# Buck.net
KiCad netlist of a schematic drawn in Altium Designer
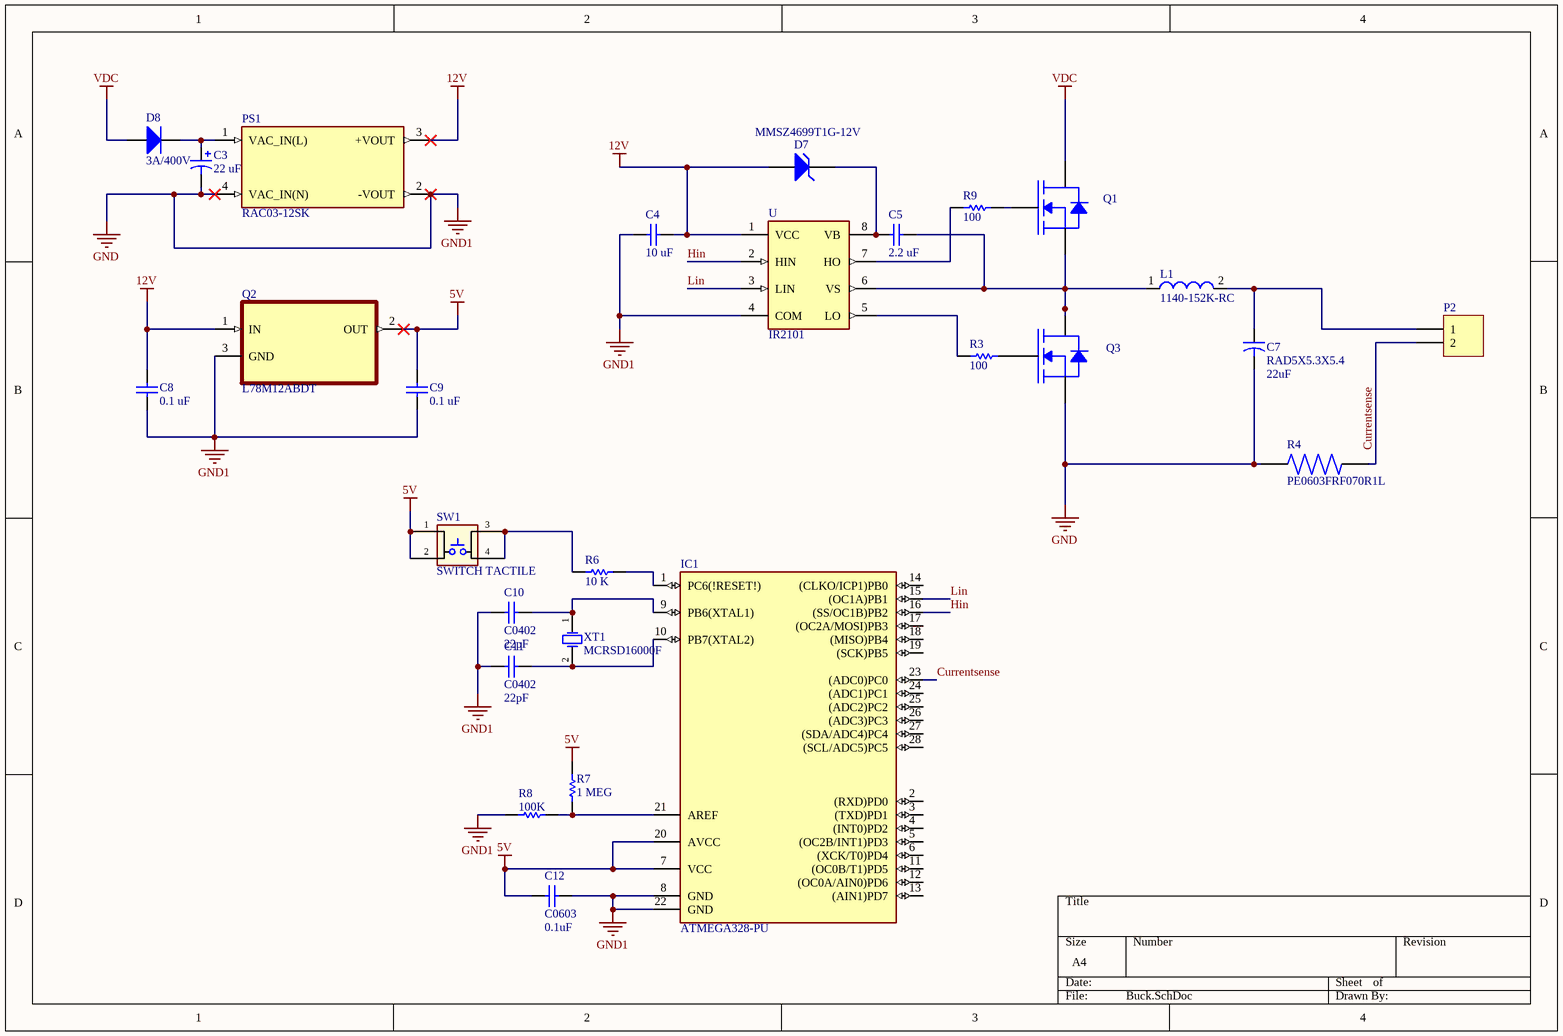
[diagram p0: Buck.SchDoc]

(export (version "E")
  (design (tool "Eeschema 10.0.6"))
  (components
    (comp (ref "C3")
      (value "22 uF")
      (footprint "CAP-12.25X25")
      (description "22 uF Electrlytic capacitor")
      (fields (field (name "Comment") "EEUED2G220") (field (name "PUBLISHER") "Altium Limited"))
      (libsource (lib "Viva") (part "EEUED2G220"))
    )
    (comp (ref "C4")
      (value "10 uF")
      (footprint "1206")
      (description "10 uF X7R Ceremic Capacitor")
      (fields (field (name "Comment") "MC1206B106K160CT") (field (name "PUBLISHER") "Sinan"))
      (libsource (lib "Viva") (part "MC1206B106K160CT"))
    )
    (comp (ref "C5")
      (value "2.2 uF")
      (footprint "0805")
      (description "2.2 uF X7R Ceremic Capacitor")
      (fields
        (field (name "TOLERANCE") "%10")
        (field (name "Comment") "C2012X7R1C225K")
        (field (name "PUBLISHER") "Sinan")
      )
      (libsource (lib "Viva") (part "C2012X7R1C225K"))
    )
    (comp (ref "C7")
      (value "22uF")
      (footprint "RAD5.3X5.3X5.0")
      (description "CAP ALUM 22UF 20% 35V SMD 5X5.3X5.4")
      (fields (field (name "MANUFACTURER") "PANASONIC") (field (name "PACKAGE REFERENCE") "RAD5X5.3X5.4"))
      (libsource (lib "CAPACITOR_LIB") (part "CAP ALUM 22UF 20% 35V SMD 5X5.3X5.4"))
    )
    (comp (ref "C8")
      (value "0.1 uF")
      (footprint "0603")
      (description "0.1uF X7R Ceramic Capacitor")
      (fields
        (field (name "TOLERANCE") "%5")
        (field (name "Comment") "*Value")
        (field (name "PUBLISHER") "Baris")
      )
      (libsource (lib "Viva") (part "C0603C104K3RACTU"))
    )
    (comp (ref "C9")
      (value "0.1 uF")
      (footprint "0603")
      (description "0.1uF X7R Ceramic Capacitor")
      (fields
        (field (name "TOLERANCE") "%5")
        (field (name "Comment") "*Value")
        (field (name "PUBLISHER") "Baris")
      )
      (libsource (lib "Viva") (part "C0603C104K3RACTU"))
    )
    (comp (ref "C10")
      (value "22pF")
      (footprint "C0402N")
      (description "CAP CER 22PF 5% 50V NP0 SMD 0402")
      (fields (field (name "MANUFACTURER") "SAMSUNG ELECTRO") (field (name "PACKAGE REFERENCE") "C0402"))
      (libsource (lib "CAPACITOR_LIB") (part "CAP CER 22PF 5% 50V NP0 SMD 0402"))
    )
    (comp (ref "C11")
      (value "22pF")
      (footprint "C0402N")
      (description "CAP CER 22PF 5% 50V NP0 SMD 0402")
      (fields (field (name "MANUFACTURER") "SAMSUNG ELECTRO") (field (name "PACKAGE REFERENCE") "C0402"))
      (libsource (lib "CAPACITOR_LIB") (part "CAP CER 22PF 5% 50V NP0 SMD 0402"))
    )
    (comp (ref "C12")
      (value "0.1uF")
      (footprint "C0603N")
      (description "CAP CER 0.1UF 10% 16V X7R SMD 0603")
      (fields (field (name "MANUFACTURER") "MURATA") (field (name "PACKAGE REFERENCE") "C0603"))
      (libsource (lib "CAPACITOR_LIB") (part "CAP CER 0.1UF 10% 16V X7R SMD 0603"))
    )
    (comp (ref "D7")
      (value "MMSZ4699T1G-12V")
      (footprint "SOD123")
      (description "DIODE ZENER 12V 500MW SOD123")
      (fields (field (name "PUBLISHER") "Baris"))
      (libsource (lib "Viva") (part "MMSZ4699T1G"))
    )
    (comp (ref "D8")
      (value "3A/400V")
      (footprint "DO201AD")
      (description "DIODE GEN PURP 400V 3A DO201AD")
      (fields
        (field (name "MANUFACTURER") "DIODES INC.")
        (field (name "Comment") "DIODE GEN PURP 400V 3A DO201AD - 1N5404")
      )
      (libsource (lib "DISCRETE_LIB") (part "DIODE GEN PURP 400V 3A DO201AD - 1N5404"))
    )
    (comp (ref "IC1")
      (value "ATMEGA328-PU")
      (footprint "DIL28")
      (description "AVR AVRÂ® ATmega Microcontroller IC 8-Bit 20MHz 32KB _16K x 16_ FLASH 28-PDIP")
      (fields (field (name "MF") "Microchip Technology"))
      (libsource (lib "ATMEGA328-PU") (part "ATMEGA328-PU"))
    )
    (comp (ref "L1")
      (value "1140-152K-RC")
      (footprint "INDRD2921W163D3810H2616P")
      (description "1.5mH Unshielded Wirewound Inductor 2.9A 324mOhm Max Radial")
      (fields (field (name "MF") "Bourns"))
      (libsource (lib "1140-152K-RC") (part "1140-152K-RC"))
    )
    (comp (ref "P2")
      (value "Konnektör")
      (footprint "250-202")
      (description "2 pos power connector")
      (fields (field (name "PUBLISHER") "Sinan"))
      (libsource (lib "Viva") (part "250-202"))
    )
    (comp (ref "PS1")
      (value "RAC03-12SK")
      (footprint "CONV_RAC03-12SK")
      (description "Enclosed AC DC Converters 1 Uitgang 12V 250mA 85 ~ 264 VAC, 120 ~ 370 VDC Input")
      (fields (field (name "MF") "Recom Power"))
      (libsource (lib "RAC03-12SK") (part "RAC03-12SK"))
    )
    (comp (ref "Q1")
      (value "LSIC1MO120E0080")
      (footprint "TO-247-3L")
      (description "LittleFuse SIC mosfet")
      (fields (field (name "PUBLISHER") "Baris"))
      (libsource (lib "Viva") (part "LSIC1MO120E0080"))
    )
    (comp (ref "Q2")
      (value "L78M12ABDT")
      (footprint "TO225P972X240-3N")
      (description "Linear Voltage Regulator IC 1 Output 500mA DPAK")
      (fields (field (name "MF") "STMicroelectronics"))
      (libsource (lib "L78M12ABDT") (part "L78M12ABDT"))
    )
    (comp (ref "Q3")
      (value "LSIC1MO120E0080")
      (footprint "TO-247-3L")
      (description "LittleFuse SIC mosfet")
      (fields (field (name "PUBLISHER") "Baris"))
      (libsource (lib "Viva") (part "LSIC1MO120E0080"))
    )
    (comp (ref "R3")
      (value "100")
      (footprint "1206")
      (description "100 ohm 1206 package resistor")
      (fields (field (name "Comment") "*Value") (field (name "PUBLISHER") "Baris"))
      (libsource (lib "Viva") (part "MC0125W12061100R"))
    )
    (comp (ref "R4")
      (value "PE0603FRF070R1L")
      (footprint "RESC1507X55N")
      (libsource (lib "PE0603FRF070R1L") (part "PE0603FRF070R1L"))
    )
    (comp (ref "R6")
      (value "10 K")
      (footprint "0603")
      (description "10k ohm 0603 package resistor")
      (fields
        (field (name "TOLERANCE") "5%")
        (field (name "Comment") "ERJ3GEYJ103V")
        (field (name "PUBLISHER") "Sinan")
      )
      (libsource (lib "Viva") (part "ERJ3GEYJ103V"))
    )
    (comp (ref "R7")
      (value "1 MEG")
      (footprint "0603")
      (description "1 MEG ohm 0603 package resistor")
      (fields (field (name "Comment") "Resistor") (field (name "PUBLISHER") "Sinan"))
      (libsource (lib "Viva") (part "MC0063W060311M"))
    )
    (comp (ref "R8")
      (value "100K")
      (footprint "0603")
      (description "100Kohm 0603package resistor")
      (fields (field (name "Comment") "MC0063W06031100K") (field (name "PUBLISHER") "Baris"))
      (libsource (lib "Viva") (part "MC0063W06031100K"))
    )
    (comp (ref "R9")
      (value "100")
      (footprint "1206")
      (description "100 ohm 1206 package resistor")
      (fields (field (name "Comment") "*Value") (field (name "PUBLISHER") "Baris"))
      (libsource (lib "Viva") (part "MC0125W12061100R"))
    )
    (comp (ref "SW1")
      (value "SWITCH TACTILE")
      (footprint "SWITCH_TACHTILE_SMD")
      (description "SWITCH TACTILE (SPST NO) TOP ACTUATED SURFACE MOUNT")
      (fields (field (name "MANUFACTURER") "C&K Components"))
      (libsource (lib "CONNECTOR_LIB") (part "SWITCH TACTILE"))
    )
    (comp (ref "U")
      (value "IR2101")
      (footprint "DIL08")
      (description "Half-Bridge Gate Driver IC Non-Inverting 8-PDIP")
      (fields (field (name "MF") "Infineon"))
      (libsource (lib "IR2101 (1)") (part "IR2101"))
    )
    (comp (ref "XT1")
      (value "MCRSD16000F")
      (footprint "XTAL_11.4MMX 4.7MM")
      (description "CRYSTAL 16MHZ 18PF")
      (fields (field (name "MANUFACTURER") "MULTICOMP"))
      (libsource (lib "DISCRETE_LIB") (part "CRYSTAL 16MHZ 18PF"))
    )
  )
  (nets
    (net (code "1") (name "/Currentsense") (class "Default")
      (node (ref "IC1") (pin "23") (pinfunction "(ADC0)PC0_23") (pintype "bidirectional"))
      (node (ref "P2") (pin "2") (pinfunction "2_2") (pintype "passive"))
      (node (ref "R4") (pin "1") (pinfunction "1_1") (pintype "passive"))
    )
    (net (code "2") (name "/Hin") (class "Default")
      (node (ref "IC1") (pin "16") (pinfunction "(SS/OC1B)PB2_16") (pintype "bidirectional"))
      (node (ref "U") (pin "2") (pinfunction "HIN_2") (pintype "input"))
    )
    (net (code "3") (name "/Lin") (class "Default")
      (node (ref "IC1") (pin "15") (pinfunction "(OC1A)PB1_15") (pintype "bidirectional"))
      (node (ref "U") (pin "3") (pinfunction "LIN_3") (pintype "input"))
    )
    (net (code "4") (name "5V") (class "Default")
      (node (ref "C12") (pin "1") (pinfunction "1_1") (pintype "passive"))
      (node (ref "C9") (pin "2") (pinfunction "2_2") (pintype "passive"))
      (node (ref "IC1") (pin "20") (pinfunction "AVCC_20") (pintype "power_in"))
      (node (ref "IC1") (pin "7") (pinfunction "VCC_7") (pintype "power_in"))
      (node (ref "Q2") (pin "2") (pinfunction "OUT_2") (pintype "output"))
      (node (ref "R7") (pin "2") (pinfunction "2_2") (pintype "passive"))
      (node (ref "SW1") (pin "1") (pinfunction "1_1") (pintype "passive"))
      (node (ref "SW1") (pin "2") (pinfunction "2_2") (pintype "passive"))
    )
    (net (code "5") (name "12V") (class "Default")
      (node (ref "C4") (pin "2") (pinfunction "2_2") (pintype "passive"))
      (node (ref "C8") (pin "2") (pinfunction "2_2") (pintype "passive"))
      (node (ref "D7") (pin "1") (pinfunction "A_1") (pintype "passive"))
      (node (ref "PS1") (pin "3") (pinfunction "+VOUT_3") (pintype "output"))
      (node (ref "Q2") (pin "1") (pinfunction "IN_1") (pintype "input"))
      (node (ref "U") (pin "1") (pinfunction "VCC_1") (pintype "power_in"))
    )
    (net (code "6") (name "GND") (class "Default")
      (node (ref "C10") (pin "1") (pinfunction "1_1") (pintype "passive"))
      (node (ref "C11") (pin "1") (pinfunction "1_1") (pintype "passive"))
      (node (ref "C12") (pin "2") (pinfunction "2_2") (pintype "passive"))
      (node (ref "C3") (pin "2") (pinfunction "2_2") (pintype "passive"))
      (node (ref "C4") (pin "1") (pinfunction "1_1") (pintype "passive"))
      (node (ref "C7") (pin "2") (pinfunction "2_2") (pintype "passive"))
      (node (ref "C8") (pin "1") (pinfunction "1_1") (pintype "passive"))
      (node (ref "C9") (pin "1") (pinfunction "1_1") (pintype "passive"))
      (node (ref "IC1") (pin "22") (pinfunction "GND_22") (pintype "power_in"))
      (node (ref "IC1") (pin "8") (pinfunction "GND_8") (pintype "power_in"))
      (node (ref "PS1") (pin "2") (pinfunction "-VOUT_2") (pintype "output"))
      (node (ref "PS1") (pin "4") (pinfunction "VAC_IN(N)_4") (pintype "input"))
      (node (ref "Q2") (pin "3") (pinfunction "GND_3") (pintype "passive"))
      (node (ref "Q3") (pin "3") (pinfunction "S_3") (pintype "passive"))
      (node (ref "R4") (pin "2") (pinfunction "2_2") (pintype "passive"))
      (node (ref "R8") (pin "2") (pinfunction "2_2") (pintype "passive"))
      (node (ref "U") (pin "4") (pinfunction "COM_4") (pintype "power_in"))
    )
    (net (code "7") (name "Net-(C7-Pad1)") (class "Default")
      (node (ref "C7") (pin "1") (pinfunction "1_1") (pintype "passive"))
      (node (ref "L1") (pin "2") (pinfunction "2_2") (pintype "passive"))
      (node (ref "P2") (pin "1") (pinfunction "1_1") (pintype "passive"))
    )
    (net (code "8") (name "Net-(D7-K)") (class "Default")
      (node (ref "C5") (pin "1") (pinfunction "1_1") (pintype "passive"))
      (node (ref "D7") (pin "2") (pinfunction "K_2") (pintype "passive"))
      (node (ref "U") (pin "8") (pinfunction "VB_8") (pintype "power_in"))
    )
    (net (code "9") (name "Net-(D8-K)") (class "Default")
      (node (ref "C3") (pin "1") (pinfunction "1_1") (pintype "passive"))
      (node (ref "D8") (pin "2") (pinfunction "K_2") (pintype "passive"))
      (node (ref "PS1") (pin "1") (pinfunction "VAC_IN(L)_1") (pintype "input"))
    )
    (net (code "10") (name "Net-(IC1-AREF)") (class "Default")
      (node (ref "IC1") (pin "21") (pinfunction "AREF_21") (pintype "passive"))
      (node (ref "R7") (pin "1") (pinfunction "1_1") (pintype "passive"))
      (node (ref "R8") (pin "1") (pinfunction "1_1") (pintype "passive"))
    )
    (net (code "11") (name "Net-(IC1-PB6(XTAL1))") (class "Default")
      (node (ref "C10") (pin "2") (pinfunction "2_2") (pintype "passive"))
      (node (ref "IC1") (pin "9") (pinfunction "PB6(XTAL1)_9") (pintype "bidirectional"))
      (node (ref "XT1") (pin "1") (pinfunction "OSC1_1") (pintype "passive"))
    )
    (net (code "12") (name "Net-(IC1-PB7(XTAL2))") (class "Default")
      (node (ref "C11") (pin "2") (pinfunction "2_2") (pintype "passive"))
      (node (ref "IC1") (pin "10") (pinfunction "PB7(XTAL2)_10") (pintype "bidirectional"))
      (node (ref "XT1") (pin "2") (pinfunction "OSC2_2") (pintype "passive"))
    )
    (net (code "13") (name "Net-(IC1-PC6(!RESET!))") (class "Default")
      (node (ref "IC1") (pin "1") (pinfunction "PC6(!RESET!)_1") (pintype "bidirectional"))
      (node (ref "R6") (pin "1") (pinfunction "1_1") (pintype "passive"))
    )
    (net (code "14") (name "Net-(Q1-G)") (class "Default")
      (node (ref "Q1") (pin "1") (pinfunction "G_1") (pintype "passive"))
      (node (ref "R9") (pin "2") (pinfunction "2_2") (pintype "passive"))
    )
    (net (code "15") (name "Net-(Q1-S)") (class "Default")
      (node (ref "C5") (pin "2") (pinfunction "2_2") (pintype "passive"))
      (node (ref "L1") (pin "1") (pinfunction "1_1") (pintype "passive"))
      (node (ref "Q1") (pin "3") (pinfunction "S_3") (pintype "passive"))
      (node (ref "Q3") (pin "2") (pinfunction "D(Tab)_2") (pintype "passive"))
      (node (ref "U") (pin "6") (pinfunction "VS_6") (pintype "output"))
    )
    (net (code "16") (name "Net-(Q3-G)") (class "Default")
      (node (ref "Q3") (pin "1") (pinfunction "G_1") (pintype "passive"))
      (node (ref "R3") (pin "2") (pinfunction "2_2") (pintype "passive"))
    )
    (net (code "17") (name "Net-(R6-Pad2)") (class "Default")
      (node (ref "R6") (pin "2") (pinfunction "2_2") (pintype "passive"))
      (node (ref "SW1") (pin "3") (pinfunction "3_3") (pintype "passive"))
      (node (ref "SW1") (pin "4") (pinfunction "4_4") (pintype "passive"))
    )
    (net (code "18") (name "Net-(U-HO)") (class "Default")
      (node (ref "R9") (pin "1") (pinfunction "1_1") (pintype "passive"))
      (node (ref "U") (pin "7") (pinfunction "HO_7") (pintype "output"))
    )
    (net (code "19") (name "Net-(U-LO)") (class "Default")
      (node (ref "R3") (pin "1") (pinfunction "1_1") (pintype "passive"))
      (node (ref "U") (pin "5") (pinfunction "LO_5") (pintype "output"))
    )
    (net (code "20") (name "VDC") (class "Default")
      (node (ref "D8") (pin "1") (pinfunction "A_1") (pintype "passive"))
      (node (ref "Q1") (pin "2") (pinfunction "D(Tab)_2") (pintype "passive"))
    )
    (net (code "21") (name "unconnected-(IC1-(ADC1)PC1-Pad24)") (class "Default")
      (node (ref "IC1") (pin "24") (pinfunction "(ADC1)PC1_24") (pintype "bidirectional"))
    )
    (net (code "22") (name "unconnected-(IC1-(ADC2)PC2-Pad25)") (class "Default")
      (node (ref "IC1") (pin "25") (pinfunction "(ADC2)PC2_25") (pintype "bidirectional"))
    )
    (net (code "23") (name "unconnected-(IC1-(ADC3)PC3-Pad26)") (class "Default")
      (node (ref "IC1") (pin "26") (pinfunction "(ADC3)PC3_26") (pintype "bidirectional"))
    )
    (net (code "24") (name "unconnected-(IC1-(AIN1)PD7-Pad13)") (class "Default")
      (node (ref "IC1") (pin "13") (pinfunction "(AIN1)PD7_13") (pintype "bidirectional"))
    )
    (net (code "25") (name "unconnected-(IC1-(CLKO{slash}ICP1)PB0-Pad14)") (class "Default")
      (node (ref "IC1") (pin "14") (pinfunction "(CLKO/ICP1)PB0_14") (pintype "bidirectional"))
    )
    (net (code "26") (name "unconnected-(IC1-(INT0)PD2-Pad4)") (class "Default")
      (node (ref "IC1") (pin "4") (pinfunction "(INT0)PD2_4") (pintype "bidirectional"))
    )
    (net (code "27") (name "unconnected-(IC1-(MISO)PB4-Pad18)") (class "Default")
      (node (ref "IC1") (pin "18") (pinfunction "(MISO)PB4_18") (pintype "bidirectional"))
    )
    (net (code "28") (name "unconnected-(IC1-(OC0A{slash}AIN0)PD6-Pad12)") (class "Default")
      (node (ref "IC1") (pin "12") (pinfunction "(OC0A/AIN0)PD6_12") (pintype "bidirectional"))
    )
    (net (code "29") (name "unconnected-(IC1-(OC0B{slash}T1)PD5-Pad11)") (class "Default")
      (node (ref "IC1") (pin "11") (pinfunction "(OC0B/T1)PD5_11") (pintype "bidirectional"))
    )
    (net (code "30") (name "unconnected-(IC1-(OC2A{slash}MOSI)PB3-Pad17)") (class "Default")
      (node (ref "IC1") (pin "17") (pinfunction "(OC2A/MOSI)PB3_17") (pintype "bidirectional"))
    )
    (net (code "31") (name "unconnected-(IC1-(OC2B{slash}INT1)PD3-Pad5)") (class "Default")
      (node (ref "IC1") (pin "5") (pinfunction "(OC2B/INT1)PD3_5") (pintype "bidirectional"))
    )
    (net (code "32") (name "unconnected-(IC1-(RXD)PD0-Pad2)") (class "Default")
      (node (ref "IC1") (pin "2") (pinfunction "(RXD)PD0_2") (pintype "bidirectional"))
    )
    (net (code "33") (name "unconnected-(IC1-(SCK)PB5-Pad19)") (class "Default")
      (node (ref "IC1") (pin "19") (pinfunction "(SCK)PB5_19") (pintype "bidirectional"))
    )
    (net (code "34") (name "unconnected-(IC1-(SCL{slash}ADC5)PC5-Pad28)") (class "Default")
      (node (ref "IC1") (pin "28") (pinfunction "(SCL/ADC5)PC5_28") (pintype "bidirectional"))
    )
    (net (code "35") (name "unconnected-(IC1-(SDA{slash}ADC4)PC4-Pad27)") (class "Default")
      (node (ref "IC1") (pin "27") (pinfunction "(SDA/ADC4)PC4_27") (pintype "bidirectional"))
    )
    (net (code "36") (name "unconnected-(IC1-(TXD)PD1-Pad3)") (class "Default")
      (node (ref "IC1") (pin "3") (pinfunction "(TXD)PD1_3") (pintype "bidirectional"))
    )
    (net (code "37") (name "unconnected-(IC1-(XCK{slash}T0)PD4-Pad6)") (class "Default")
      (node (ref "IC1") (pin "6") (pinfunction "(XCK/T0)PD4_6") (pintype "bidirectional"))
    )
  )
)
